# Sheet2-USB.net
KiCad netlist of a schematic drawn in Altium Designer
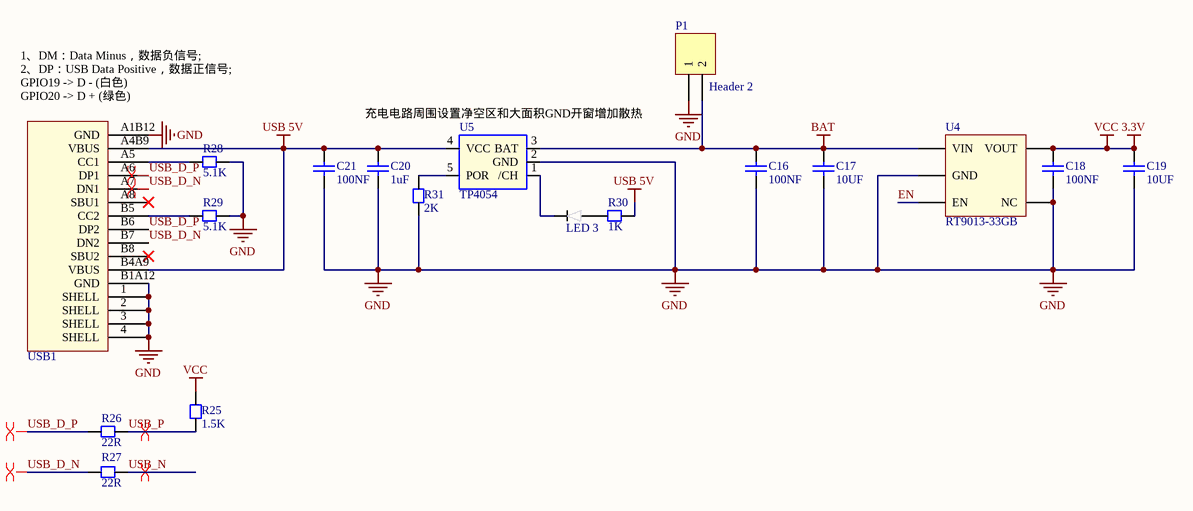
[diagram p0: Sheet2-USB.SchDoc]

(export (version "E")
  (design (tool "Eeschema 10.0.6"))
  (components
    (comp (ref "C16")
      (value "100NF")
      (footprint "CC1608-0603")
      (description "0603封装的电容")
      (fields (field (name "PUBLISHER") "Altium Limited"))
      (libsource (lib "base") (part "Cap Chip 0603"))
    )
    (comp (ref "C17")
      (value "10UF")
      (footprint "CC1608-0603")
      (description "0603封装的电容")
      (fields (field (name "PUBLISHER") "Altium Limited"))
      (libsource (lib "base") (part "Cap Chip 0603"))
    )
    (comp (ref "C18")
      (value "100NF")
      (footprint "CC1608-0603")
      (description "0603封装的电容")
      (fields (field (name "PUBLISHER") "Altium Limited"))
      (libsource (lib "base") (part "Cap Chip 0603"))
    )
    (comp (ref "C19")
      (value "10UF")
      (footprint "CC1608-0603")
      (description "0603封装的电容")
      (fields (field (name "PUBLISHER") "Altium Limited"))
      (libsource (lib "base") (part "Cap Chip 0603"))
    )
    (comp (ref "C20")
      (value "1uF")
      (footprint "CC1608-0603")
      (description "0603封装的电容")
      (fields (field (name "PUBLISHER") "Altium Limited"))
      (libsource (lib "base") (part "Cap Chip 0603"))
    )
    (comp (ref "C21")
      (value "100NF")
      (footprint "CC1608-0603")
      (description "0603封装的电容")
      (fields (field (name "PUBLISHER") "Altium Limited"))
      (libsource (lib "base") (part "Cap Chip 0603"))
    )
    (comp (ref "LED 3") (value "LED 0603") (footprint "LED 0603") (libsource (lib "base") (part "LED 0603")))
    (comp (ref "P1")
      (value "Header 2")
      (footprint "HX2.54-2")
      (description "Header, 2-Pin")
      (fields (field (name "PUBLISHER") "Altium Limited"))
      (libsource (lib "Connectors") (part "Header 2"))
    )
    (comp (ref "R25")
      (value "1.5K")
      (footprint "CR1608-0603")
      (description "0603封装电阻")
      (fields (field (name "PUBLISHER") "Altium Limited"))
      (libsource (lib "") (part "Resistor Chip 0603_1"))
    )
    (comp (ref "R26")
      (value "22R")
      (footprint "CR1608-0603")
      (description "0603封装电阻")
      (fields (field (name "PUBLISHER") "Altium Limited"))
      (libsource (lib "base") (part "Resistor Chip 0603"))
    )
    (comp (ref "R27")
      (value "22R")
      (footprint "CR1608-0603")
      (description "0603封装电阻")
      (fields (field (name "PUBLISHER") "Altium Limited"))
      (libsource (lib "base") (part "Resistor Chip 0603"))
    )
    (comp (ref "R28")
      (value "5.1K")
      (footprint "CR1608-0603")
      (description "0603封装电阻")
      (fields (field (name "PUBLISHER") "Altium Limited"))
      (libsource (lib "base") (part "Resistor Chip 0603"))
    )
    (comp (ref "R29")
      (value "5.1K")
      (footprint "CR1608-0603")
      (description "0603封装电阻")
      (fields (field (name "PUBLISHER") "Altium Limited"))
      (libsource (lib "base") (part "Resistor Chip 0603"))
    )
    (comp (ref "R30")
      (value "1K")
      (footprint "CR1608-0603")
      (description "0603封装电阻")
      (fields (field (name "PUBLISHER") "Altium Limited"))
      (libsource (lib "base") (part "Resistor Chip 0603"))
    )
    (comp (ref "R31")
      (value "2K")
      (footprint "CR1608-0603")
      (description "0603封装电阻")
      (fields (field (name "PUBLISHER") "Altium Limited"))
      (libsource (lib "") (part "Resistor Chip 0603_1"))
    )
    (comp (ref "U4")
      (value "RT9013-33GB")
      (footprint "SOT23-5")
      (description "LDO 2.2-5.2V IN 500Ma OUT SOT23-5")
      (libsource (lib "power-chip") (part "RT9013-33GB"))
    )
    (comp (ref "U5")
      (value "TP4054")
      (footprint "SOT23-5")
      (description "迷你充电IC SOT-23-5")
      (libsource (lib "power-chip") (part "TP4054"))
    )
    (comp (ref "USB1")
      (value "Tpye-c 16P")
      (footprint "TYPE-C 16P")
      (description "16P 封装的TYPE -c接口 4固定插脚 双向")
      (libsource (lib "Connectors") (part "Tpye-c 16P"))
    )
  )
  (nets
    (net (code "1") (name "/EN") (class "Default")
      (node (ref "U4") (pin "3") (pinfunction "EN_3") (pintype "passive"))
    )
    (net (code "2") (name "/USB_D_N") (class "Default")
      (node (ref "R27") (pin "2") (pinfunction "2_2") (pintype "passive"))
      (node (ref "USB1") (pin "A7") (pinfunction "DN1_A7") (pintype "power_in"))
      (node (ref "USB1") (pin "B7") (pinfunction "DN2_B7") (pintype "power_in"))
    )
    (net (code "3") (name "/USB_D_P") (class "Default")
      (node (ref "R26") (pin "2") (pinfunction "2_2") (pintype "passive"))
      (node (ref "USB1") (pin "A6") (pinfunction "DP1_A6") (pintype "power_in"))
      (node (ref "USB1") (pin "B6") (pinfunction "DP2_B6") (pintype "power_in"))
    )
    (net (code "4") (name "/USB_N") (class "Default")
      (node (ref "R27") (pin "1") (pinfunction "1_1") (pintype "passive"))
    )
    (net (code "5") (name "/USB_P") (class "Default")
      (node (ref "R25") (pin "2") (pinfunction "2_2") (pintype "passive"))
      (node (ref "R26") (pin "1") (pinfunction "1_1") (pintype "passive"))
    )
    (net (code "6") (name "3.3V") (class "Default")
      (node (ref "C18") (pin "2") (pinfunction "2_2") (pintype "passive"))
      (node (ref "C19") (pin "2") (pinfunction "2_2") (pintype "passive"))
      (node (ref "R25") (pin "1") (pinfunction "1_1") (pintype "passive"))
      (node (ref "U4") (pin "5") (pinfunction "VOUT_5") (pintype "passive"))
    )
    (net (code "7") (name "BAT") (class "Default")
      (node (ref "C16") (pin "2") (pinfunction "2_2") (pintype "passive"))
      (node (ref "C17") (pin "2") (pinfunction "2_2") (pintype "passive"))
      (node (ref "P1") (pin "2") (pinfunction "2_2") (pintype "passive"))
      (node (ref "U4") (pin "1") (pinfunction "VIN_1") (pintype "passive"))
      (node (ref "U5") (pin "3") (pinfunction "BAT_3") (pintype "passive"))
    )
    (net (code "8") (name "GND") (class "Default")
      (node (ref "C16") (pin "1") (pinfunction "1_1") (pintype "passive"))
      (node (ref "C17") (pin "1") (pinfunction "1_1") (pintype "passive"))
      (node (ref "C18") (pin "1") (pinfunction "1_1") (pintype "passive"))
      (node (ref "C19") (pin "1") (pinfunction "1_1") (pintype "passive"))
      (node (ref "C20") (pin "1") (pinfunction "1_1") (pintype "passive"))
      (node (ref "C21") (pin "1") (pinfunction "1_1") (pintype "passive"))
      (node (ref "P1") (pin "1") (pinfunction "1_1") (pintype "passive"))
      (node (ref "R28") (pin "1") (pinfunction "1_1") (pintype "passive"))
      (node (ref "R29") (pin "1") (pinfunction "1_1") (pintype "passive"))
      (node (ref "R31") (pin "2") (pinfunction "2_2") (pintype "passive"))
      (node (ref "U4") (pin "2") (pinfunction "GND_2") (pintype "passive"))
      (node (ref "U4") (pin "4") (pinfunction "NC_4") (pintype "passive"))
      (node (ref "U5") (pin "2") (pinfunction "GND_2") (pintype "passive"))
      (node (ref "USB1") (pin "1") (pinfunction "SHELL_1") (pintype "power_in"))
      (node (ref "USB1") (pin "2") (pinfunction "SHELL_2") (pintype "power_in"))
      (node (ref "USB1") (pin "3") (pinfunction "SHELL_3") (pintype "power_in"))
      (node (ref "USB1") (pin "4") (pinfunction "SHELL_4") (pintype "power_in"))
      (node (ref "USB1") (pin "A1B12") (pinfunction "GND_A1B12") (pintype "power_in"))
      (node (ref "USB1") (pin "B1A12") (pinfunction "GND_B1A12") (pintype "power_in"))
    )
    (net (code "9") (name "Net-(LED 3-Pad1)") (class "Default")
      (node (ref "LED 3") (pin "1") (pinfunction "1_1") (pintype "passive"))
      (node (ref "R30") (pin "2") (pinfunction "2_2") (pintype "passive"))
    )
    (net (code "10") (name "Net-(U5-POR)") (class "Default")
      (node (ref "R31") (pin "1") (pinfunction "1_1") (pintype "passive"))
      (node (ref "U5") (pin "5") (pinfunction "POR_5") (pintype "passive"))
    )
    (net (code "11") (name "Net-(U5-{slash}CH)") (class "Default")
      (node (ref "LED 3") (pin "2") (pinfunction "2_2") (pintype "passive"))
      (node (ref "U5") (pin "1") (pinfunction "/CH_1") (pintype "passive"))
    )
    (net (code "12") (name "Net-(USB1-CC1)") (class "Default")
      (node (ref "R28") (pin "2") (pinfunction "2_2") (pintype "passive"))
      (node (ref "USB1") (pin "A5") (pinfunction "CC1_A5") (pintype "power_in"))
    )
    (net (code "13") (name "Net-(USB1-CC2)") (class "Default")
      (node (ref "R29") (pin "2") (pinfunction "2_2") (pintype "passive"))
      (node (ref "USB1") (pin "B5") (pinfunction "CC2_B5") (pintype "power_in"))
    )
    (net (code "14") (name "USB 5V") (class "Default")
      (node (ref "C20") (pin "2") (pinfunction "2_2") (pintype "passive"))
      (node (ref "C21") (pin "2") (pinfunction "2_2") (pintype "passive"))
      (node (ref "R30") (pin "1") (pinfunction "1_1") (pintype "passive"))
      (node (ref "U5") (pin "4") (pinfunction "VCC_4") (pintype "passive"))
      (node (ref "USB1") (pin "A4B9") (pinfunction "VBUS_A4B9") (pintype "power_in"))
      (node (ref "USB1") (pin "B4A9") (pinfunction "VBUS_B4A9") (pintype "power_in"))
    )
    (net (code "15") (name "unconnected-(USB1-SBU1-PadA8)") (class "Default")
      (node (ref "USB1") (pin "A8") (pinfunction "SBU1_A8") (pintype "power_in+no_connect"))
    )
    (net (code "16") (name "unconnected-(USB1-SBU2-PadB8)") (class "Default")
      (node (ref "USB1") (pin "B8") (pinfunction "SBU2_B8") (pintype "power_in+no_connect"))
    )
  )
)
